# Placa_Final_Embebidos_Hoja3.net
KiCad netlist of a schematic drawn in Altium Designer
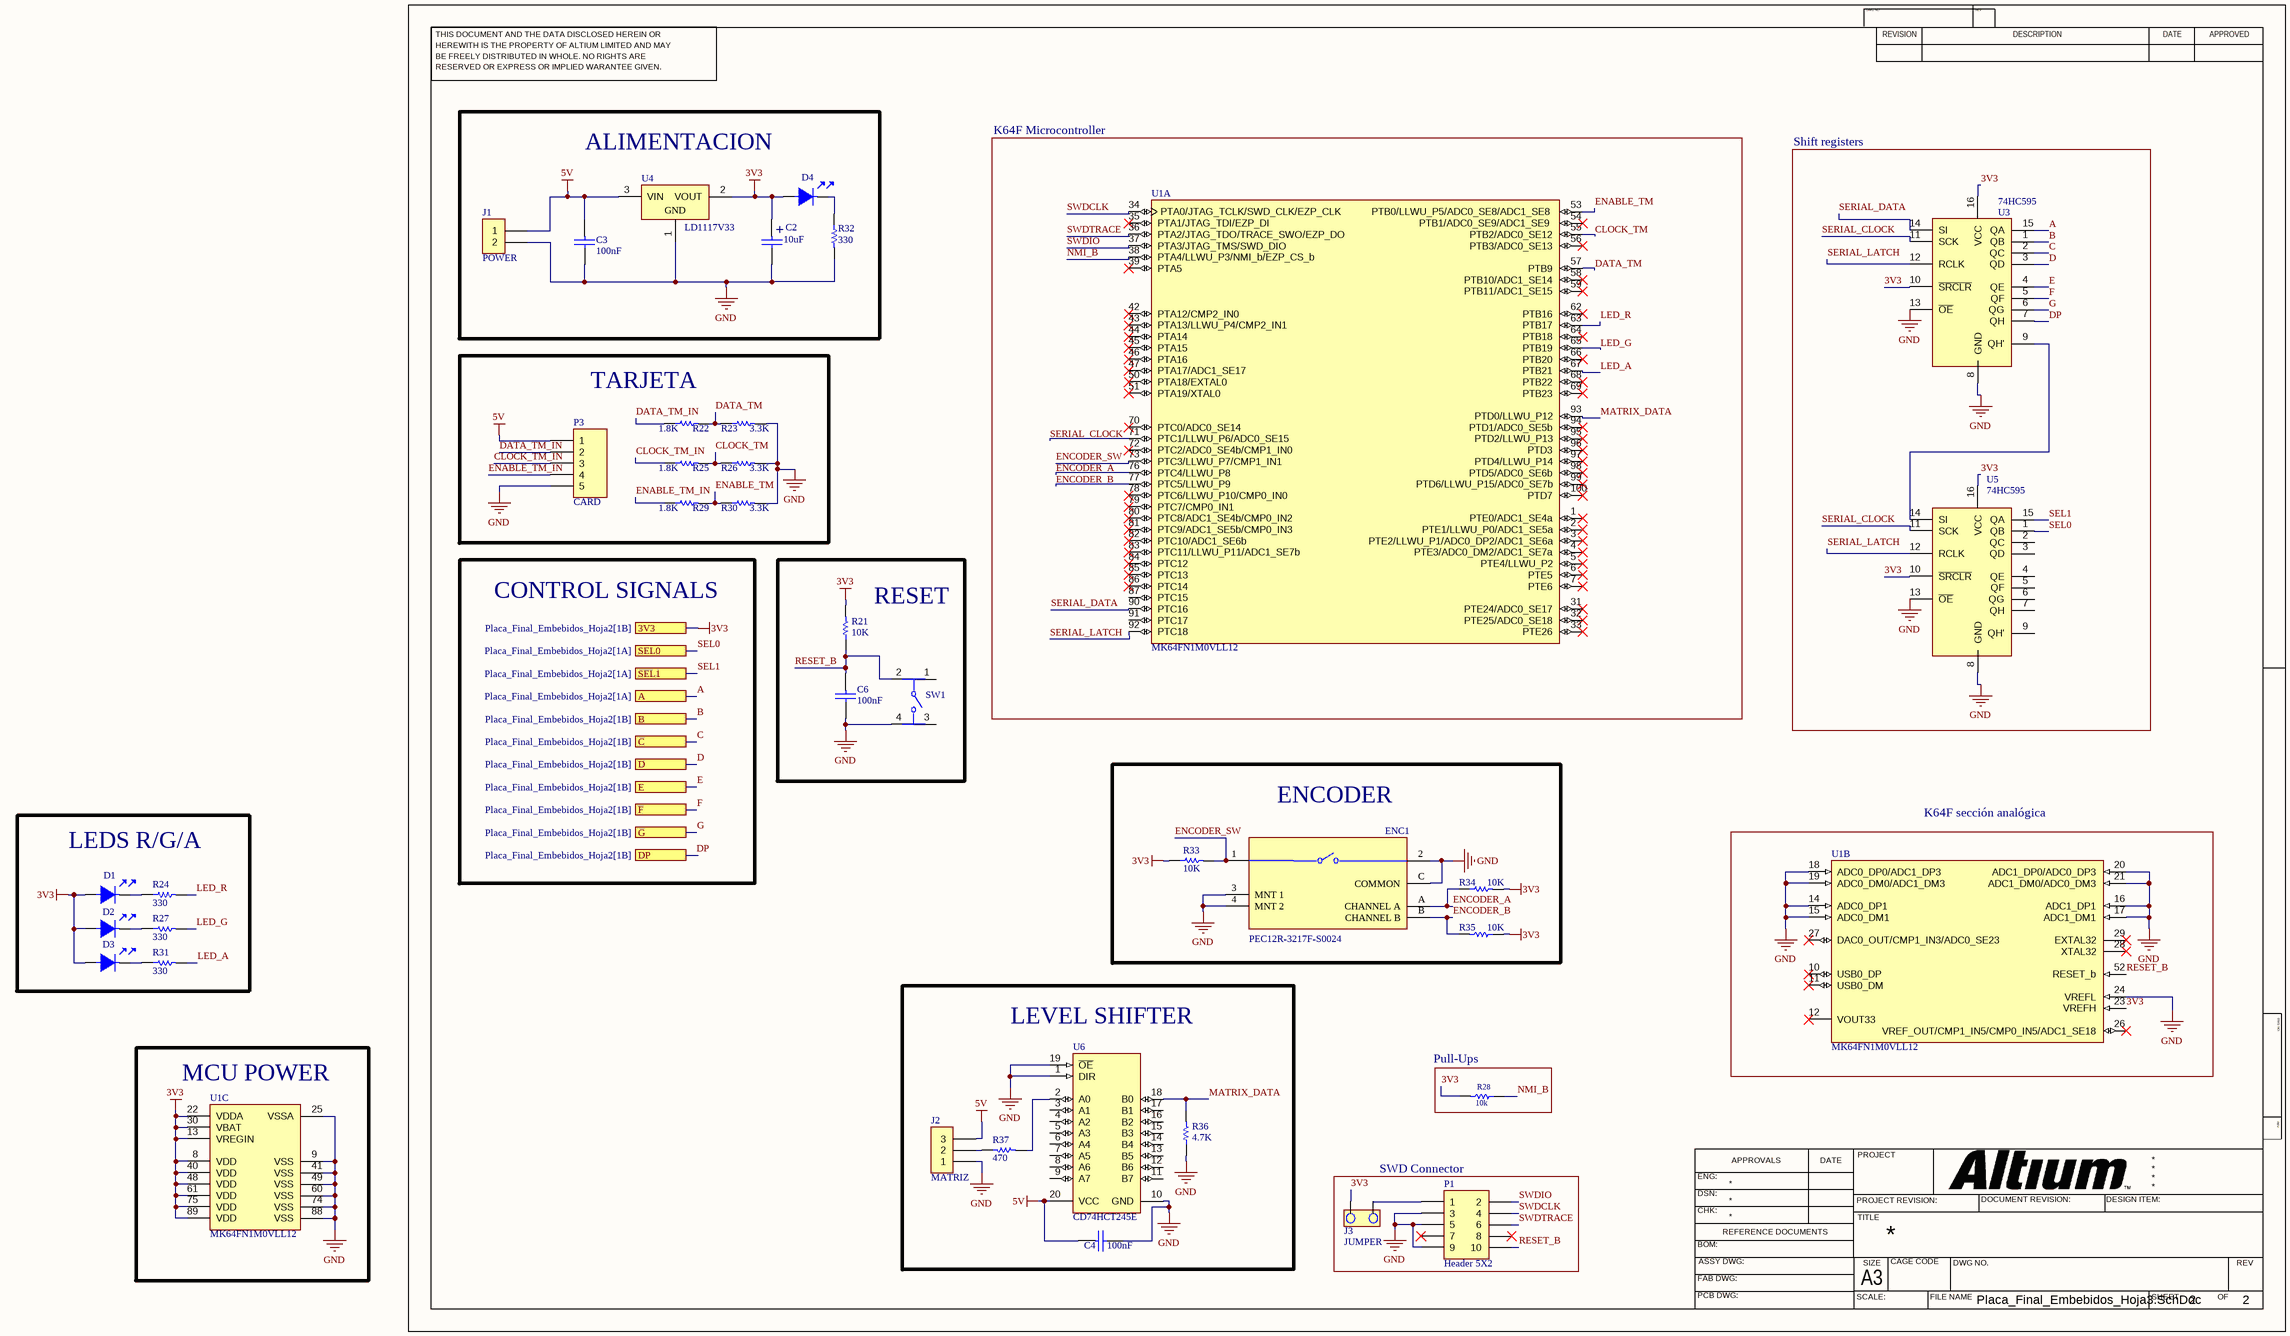
[diagram p0: Placa_Final_Embebidos_Hoja3.SchDoc]

(export (version "E")
  (design (tool "Eeschema 10.0.6"))
  (components
    (comp (ref "C2") (value "10uF") (footprint "CAP100RP") (libsource (lib "LIB PIO IX") (part "CAPPOL")))
    (comp (ref "C3") (value "100nF") (footprint "CAP200") (libsource (lib "LIB PIO IX") (part "CAP")))
    (comp (ref "C4") (value "100nF") (footprint "CAP200") (libsource (lib "LIB PIO IX") (part "CAP")))
    (comp (ref "C6") (value "100nF") (footprint "CAP200") (libsource (lib "LIB PIO IX") (part "CAP")))
    (comp (ref "D1") (value "~") (footprint "LED3") (libsource (lib "LIB PIO IX") (part "LED")))
    (comp (ref "D2") (value "~") (footprint "LED3") (libsource (lib "LIB PIO IX") (part "LED")))
    (comp (ref "D3") (value "~") (footprint "LED3") (libsource (lib "LIB PIO IX") (part "LED")))
    (comp (ref "D4") (value "~") (footprint "LED3") (libsource (lib "LIB PIO IX") (part "LED")))
    (comp (ref "ENC1")
      (value "PEC12R-3217F-S0024")
      (footprint "FP-PEC12R-3217F-S0024-MFG")
      (description "ROTARY ENCODER")
      (libsource (lib "Altium Content Vault") (part "795c46dd6d7d77f565e7c060d07d204"))
    )
    (comp (ref "J1") (value "POWER") (footprint "BORNERA2") (libsource (lib "LIBEBAL") (part "BORNERA 2")))
    (comp (ref "J2") (value "MATRIZ") (footprint "SIP3") (libsource (lib "LIBEBAL") (part "CON3")))
    (comp (ref "J3") (value "JUMPER") (footprint "JUMPER2") (libsource (lib "LIBEBAL") (part "JUMPER")))
    (comp (ref "P1")
      (value "Header 5X2")
      (footprint "HDR2X5")
      (description "Header, 5-Pin, Dual row")
      (fields (field (name "PUBLISHER") "Altium Limited"))
      (libsource (lib "Miscellaneous Connectors") (part "Header 5X2"))
    )
    (comp (ref "P3")
      (value "CARD")
      (footprint "HDR1X5")
      (description "Header, 5-Pin")
      (fields (field (name "PUBLISHER") "Altium Limited"))
      (libsource (lib "Miscellaneous Connectors") (part "Header 5"))
    )
    (comp (ref "R21") (value "10K") (footprint "RES400") (libsource (lib "LIB PIO IX") (part "RES")))
    (comp (ref "R22") (value "1.8K") (footprint "RES400") (libsource (lib "LIB PIO IX") (part "RES")))
    (comp (ref "R23") (value "3.3K") (footprint "RES400") (libsource (lib "LIB PIO IX") (part "RES")))
    (comp (ref "R24") (value "330") (footprint "RES400") (libsource (lib "LIB PIO IX") (part "RES")))
    (comp (ref "R25") (value "1.8K") (footprint "RES400") (libsource (lib "LIB PIO IX") (part "RES")))
    (comp (ref "R26") (value "3.3K") (footprint "RES400") (libsource (lib "LIB PIO IX") (part "RES")))
    (comp (ref "R27") (value "330") (footprint "RES400") (libsource (lib "LIB PIO IX") (part "RES")))
    (comp (ref "R28") (value "10k") (footprint "RES400") (libsource (lib "LIB PIO IX") (part "RES")))
    (comp (ref "R29") (value "1.8K") (footprint "RES400") (libsource (lib "LIB PIO IX") (part "RES")))
    (comp (ref "R30") (value "3.3K") (footprint "RES400") (libsource (lib "LIB PIO IX") (part "RES")))
    (comp (ref "R31") (value "330") (footprint "RES400") (libsource (lib "LIB PIO IX") (part "RES")))
    (comp (ref "R32") (value "330") (footprint "RES400") (libsource (lib "LIB PIO IX") (part "RES")))
    (comp (ref "R33") (value "10K") (footprint "RES400") (libsource (lib "LIB PIO IX") (part "RES")))
    (comp (ref "R34") (value "10K") (footprint "RES400") (libsource (lib "LIB PIO IX") (part "RES")))
    (comp (ref "R35") (value "10K") (footprint "RES400") (libsource (lib "LIB PIO IX") (part "RES")))
    (comp (ref "R36") (value "4.7K") (footprint "RES400") (libsource (lib "LIB PIO IX") (part "RES")))
    (comp (ref "R37") (value "470") (footprint "RES400") (libsource (lib "LIB PIO IX") (part "RES")))
    (comp (ref "SW1")
      (value "~")
      (footprint "FP-B3F-1055-MFG")
      (description "SWITCH TACTILE SPST-NO 0.05A 24V")
      (libsource (lib "Altium Content Vault") (part "b8895f3f4cefb76e1819d2863dba89b"))
    )
    (comp (ref "U1")
      (value "MK64FN1M0VLL12")
      (footprint "PCB_BOARD_K64F_MIRROR:K64F_DevBoard_Headers_MIRROR")
      (fields (field (name "MANUFACTURER") "Freescale Semiconductor"))
      (libsource (lib "K64F_Board_MIRROR") (part "CMP-0182-00049-1"))
    )
    (comp (ref "U3") (value "74HC595") (footprint "DIP16") (libsource (lib "LIBEBAL") (part "74HC595")))
    (comp (ref "U4")
      (value "LD1117V33")
      (footprint "TO220")
      (description "Fixed Low Drop Positive Voltage Regulator, 3.3V, 3-Pin TO-220")
      (libsource (lib "Altium Content Vault") (part "PM-REG-LD1117V-SIL3"))
    )
    (comp (ref "U5") (value "74HC595") (footprint "DIP16") (libsource (lib "LIBEBAL") (part "74HC595")))
    (comp (ref "U6")
      (value "CD74HCT245E")
      (footprint "N0020A")
      (description "High Speed CMOS Logic Non-Inverting Octal-Bus Transceiver with 3-State Outpus, N0020A, TUBE")
      (fields
        (field (name "GENERIC PART NUMBER") "CD74HCT245")
        (field (name "MANUFACTURER") "Texas Instruments")
      )
      (libsource (lib "Altium Content Vault") (part "TI-CD54_74XXX245_640-20"))
    )
  )
  (nets
    (net (code "1") (name "/A") (class "Default")
      (node (ref "U3") (pin "15") (pinfunction "QA_15") (pintype "passive"))
    )
    (net (code "2") (name "/B") (class "Default")
      (node (ref "U3") (pin "1") (pinfunction "QB_1") (pintype "passive"))
    )
    (net (code "3") (name "/C") (class "Default")
      (node (ref "U3") (pin "2") (pinfunction "QC_2") (pintype "passive"))
    )
    (net (code "4") (name "/CLOCK_TM") (class "Default")
      (node (ref "R25") (pin "2") (pinfunction "2_2") (pintype "passive"))
      (node (ref "R26") (pin "1") (pinfunction "1_1") (pintype "passive"))
      (node (ref "U1") (pin "55") (pinfunction "PTB2/ADC0_SE12_55") (pintype "bidirectional"))
    )
    (net (code "5") (name "/CLOCK_TM_IN") (class "Default")
      (node (ref "P3") (pin "3") (pinfunction "3_3") (pintype "passive"))
      (node (ref "R25") (pin "1") (pinfunction "1_1") (pintype "passive"))
    )
    (net (code "6") (name "/D") (class "Default")
      (node (ref "U3") (pin "3") (pinfunction "QD_3") (pintype "passive"))
    )
    (net (code "7") (name "/DATA_TM") (class "Default")
      (node (ref "R22") (pin "2") (pinfunction "2_2") (pintype "passive"))
      (node (ref "R23") (pin "1") (pinfunction "1_1") (pintype "passive"))
      (node (ref "U1") (pin "57") (pinfunction "PTB9_57") (pintype "bidirectional"))
    )
    (net (code "8") (name "/DATA_TM_IN") (class "Default")
      (node (ref "P3") (pin "2") (pinfunction "2_2") (pintype "passive"))
      (node (ref "R22") (pin "1") (pinfunction "1_1") (pintype "passive"))
    )
    (net (code "9") (name "/DP") (class "Default")
      (node (ref "U3") (pin "7") (pinfunction "QH_7") (pintype "passive"))
    )
    (net (code "10") (name "/E") (class "Default")
      (node (ref "U3") (pin "4") (pinfunction "QE_4") (pintype "passive"))
    )
    (net (code "11") (name "/ENABLE_TM") (class "Default")
      (node (ref "R29") (pin "2") (pinfunction "2_2") (pintype "passive"))
      (node (ref "R30") (pin "1") (pinfunction "1_1") (pintype "passive"))
      (node (ref "U1") (pin "53") (pinfunction "PTB0/LLWU_P5/ADC0_SE8/ADC1_SE8_53") (pintype "bidirectional"))
    )
    (net (code "12") (name "/ENABLE_TM_IN") (class "Default")
      (node (ref "P3") (pin "4") (pinfunction "4_4") (pintype "passive"))
      (node (ref "R29") (pin "1") (pinfunction "1_1") (pintype "passive"))
    )
    (net (code "13") (name "/ENCODER_A") (class "Default")
      (node (ref "ENC1") (pin "A") (pinfunction "CHANNEL_A_A") (pintype "passive"))
      (node (ref "R34") (pin "1") (pinfunction "1_1") (pintype "passive"))
      (node (ref "U1") (pin "76") (pinfunction "PTC4/LLWU_P8_76") (pintype "bidirectional"))
    )
    (net (code "14") (name "/ENCODER_B") (class "Default")
      (node (ref "ENC1") (pin "B") (pinfunction "CHANNEL_B_B") (pintype "passive"))
      (node (ref "R35") (pin "2") (pinfunction "2_2") (pintype "passive"))
      (node (ref "U1") (pin "77") (pinfunction "PTC5/LLWU_P9_77") (pintype "bidirectional"))
    )
    (net (code "15") (name "/ENCODER_SW") (class "Default")
      (node (ref "ENC1") (pin "1") (pinfunction "1_1") (pintype "passive"))
      (node (ref "R33") (pin "2") (pinfunction "2_2") (pintype "passive"))
      (node (ref "U1") (pin "73") (pinfunction "PTC3/LLWU_P7/CMP1_IN1_73") (pintype "bidirectional"))
    )
    (net (code "16") (name "/F") (class "Default")
      (node (ref "U3") (pin "5") (pinfunction "QF_5") (pintype "passive"))
    )
    (net (code "17") (name "/G") (class "Default")
      (node (ref "U3") (pin "6") (pinfunction "QG_6") (pintype "passive"))
    )
    (net (code "18") (name "/LED_A") (class "Default")
      (node (ref "R31") (pin "2") (pinfunction "2_2") (pintype "passive"))
      (node (ref "U1") (pin "67") (pinfunction "PTB21_67") (pintype "bidirectional"))
    )
    (net (code "19") (name "/LED_G") (class "Default")
      (node (ref "R27") (pin "2") (pinfunction "2_2") (pintype "passive"))
      (node (ref "U1") (pin "65") (pinfunction "PTB19_65") (pintype "bidirectional"))
    )
    (net (code "20") (name "/LED_R") (class "Default")
      (node (ref "R24") (pin "2") (pinfunction "2_2") (pintype "passive"))
      (node (ref "U1") (pin "63") (pinfunction "PTB17_63") (pintype "bidirectional"))
    )
    (net (code "21") (name "/MATRIX_DATA") (class "Default")
      (node (ref "R36") (pin "2") (pinfunction "2_2") (pintype "passive"))
      (node (ref "U1") (pin "93") (pinfunction "PTD0/LLWU_P12_93") (pintype "bidirectional"))
      (node (ref "U6") (pin "18") (pinfunction "B0_18") (pintype "bidirectional"))
    )
    (net (code "22") (name "/NMI_B") (class "Default")
      (node (ref "R28") (pin "1") (pinfunction "1_1") (pintype "passive"))
      (node (ref "U1") (pin "38") (pinfunction "PTA4/LLWU_P3/NMI_b/EZP_CS_b_38") (pintype "bidirectional"))
    )
    (net (code "23") (name "/RESET_B") (class "Default")
      (node (ref "C6") (pin "1") (pinfunction "1_1") (pintype "passive"))
      (node (ref "P1") (pin "10") (pinfunction "10_10") (pintype "passive"))
      (node (ref "R21") (pin "1") (pinfunction "1_1") (pintype "passive"))
      (node (ref "SW1") (pin "2") (pinfunction "2_2") (pintype "passive"))
      (node (ref "U1") (pin "52") (pinfunction "RESET_b_52") (pintype "input"))
    )
    (net (code "24") (name "/SEL0") (class "Default")
      (node (ref "U5") (pin "1") (pinfunction "QB_1") (pintype "passive"))
    )
    (net (code "25") (name "/SEL1") (class "Default")
      (node (ref "U5") (pin "15") (pinfunction "QA_15") (pintype "passive"))
    )
    (net (code "26") (name "/SERIAL_CLOCK") (class "Default")
      (node (ref "U1") (pin "71") (pinfunction "PTC1/LLWU_P6/ADC0_SE15_71") (pintype "bidirectional"))
      (node (ref "U3") (pin "11") (pinfunction "SCK_11") (pintype "passive"))
      (node (ref "U5") (pin "11") (pinfunction "SCK_11") (pintype "passive"))
    )
    (net (code "27") (name "/SERIAL_DATA") (class "Default")
      (node (ref "U1") (pin "90") (pinfunction "PTC16_90") (pintype "bidirectional"))
      (node (ref "U3") (pin "14") (pinfunction "SI_14") (pintype "passive"))
    )
    (net (code "28") (name "/SERIAL_LATCH") (class "Default")
      (node (ref "U1") (pin "92") (pinfunction "PTC18_92") (pintype "bidirectional"))
      (node (ref "U3") (pin "12") (pinfunction "RCLK_12") (pintype "passive"))
      (node (ref "U5") (pin "12") (pinfunction "RCLK_12") (pintype "passive"))
    )
    (net (code "29") (name "/SWDCLK") (class "Default")
      (node (ref "P1") (pin "4") (pinfunction "4_4") (pintype "passive"))
      (node (ref "U1") (pin "34") (pinfunction "PTA0/JTAG_TCLK/SWD_CLK/EZP_CLK_34") (pintype "bidirectional"))
    )
    (net (code "30") (name "/SWDIO") (class "Default")
      (node (ref "P1") (pin "2") (pinfunction "2_2") (pintype "passive"))
      (node (ref "U1") (pin "37") (pinfunction "PTA3/JTAG_TMS/SWD_DIO_37") (pintype "bidirectional"))
    )
    (net (code "31") (name "/SWDTRACE") (class "Default")
      (node (ref "P1") (pin "6") (pinfunction "6_6") (pintype "passive"))
      (node (ref "U1") (pin "36") (pinfunction "PTA2/JTAG_TDO/TRACE_SWO/EZP_DO_36") (pintype "bidirectional"))
    )
    (net (code "32") (name "3V3") (class "Default")
      (node (ref "C2") (pin "1") (pinfunction "1_1") (pintype "passive"))
      (node (ref "D1") (pin "1") (pinfunction "1_1") (pintype "passive"))
      (node (ref "D2") (pin "1") (pinfunction "1_1") (pintype "passive"))
      (node (ref "D3") (pin "1") (pinfunction "1_1") (pintype "passive"))
      (node (ref "D4") (pin "1") (pinfunction "1_1") (pintype "passive"))
      (node (ref "J3") (pin "1") (pinfunction "1_1") (pintype "passive"))
      (node (ref "R21") (pin "2") (pinfunction "2_2") (pintype "passive"))
      (node (ref "R28") (pin "2") (pinfunction "2_2") (pintype "passive"))
      (node (ref "R33") (pin "1") (pinfunction "1_1") (pintype "passive"))
      (node (ref "R34") (pin "2") (pinfunction "2_2") (pintype "passive"))
      (node (ref "R35") (pin "1") (pinfunction "1_1") (pintype "passive"))
      (node (ref "U1") (pin "13") (pinfunction "VREGIN_13") (pintype "power_in"))
      (node (ref "U1") (pin "22") (pinfunction "VDDA_22") (pintype "power_in"))
      (node (ref "U1") (pin "23") (pinfunction "VREFH_23") (pintype "input"))
      (node (ref "U1") (pin "30") (pinfunction "VBAT_30") (pintype "power_in"))
      (node (ref "U1") (pin "40") (pinfunction "VDD_40") (pintype "power_in"))
      (node (ref "U1") (pin "48") (pinfunction "VDD_48") (pintype "power_in"))
      (node (ref "U1") (pin "61") (pinfunction "VDD_61") (pintype "power_in"))
      (node (ref "U1") (pin "75") (pinfunction "VDD_75") (pintype "power_in"))
      (node (ref "U1") (pin "8") (pinfunction "VDD_8") (pintype "power_in"))
      (node (ref "U1") (pin "89") (pinfunction "VDD_89") (pintype "power_in"))
      (node (ref "U3") (pin "10") (pinfunction "~{SRCLR}_10") (pintype "passive"))
      (node (ref "U3") (pin "16") (pinfunction "VCC_16") (pintype "passive"))
      (node (ref "U4") (pin "2") (pinfunction "VOUT_2") (pintype "power_in"))
      (node (ref "U5") (pin "10") (pinfunction "~{SRCLR}_10") (pintype "passive"))
      (node (ref "U5") (pin "16") (pinfunction "VCC_16") (pintype "passive"))
    )
    (net (code "33") (name "5V") (class "Default")
      (node (ref "C3") (pin "1") (pinfunction "1_1") (pintype "passive"))
      (node (ref "C4") (pin "1") (pinfunction "1_1") (pintype "passive"))
      (node (ref "J1") (pin "1") (pinfunction "1_1") (pintype "passive"))
      (node (ref "J2") (pin "3") (pinfunction "3_3") (pintype "passive"))
      (node (ref "P3") (pin "1") (pinfunction "1_1") (pintype "passive"))
      (node (ref "U4") (pin "3") (pinfunction "VIN_3") (pintype "power_in"))
      (node (ref "U6") (pin "20") (pinfunction "VCC_20") (pintype "power_in"))
    )
    (net (code "34") (name "GND") (class "Default")
      (node (ref "C2") (pin "2") (pinfunction "2_2") (pintype "passive"))
      (node (ref "C3") (pin "2") (pinfunction "2_2") (pintype "passive"))
      (node (ref "C4") (pin "2") (pinfunction "2_2") (pintype "passive"))
      (node (ref "C6") (pin "2") (pinfunction "2_2") (pintype "passive"))
      (node (ref "ENC1") (pin "2") (pinfunction "2_2") (pintype "passive"))
      (node (ref "ENC1") (pin "3") (pinfunction "MNT_1_3") (pintype "passive"))
      (node (ref "ENC1") (pin "4") (pinfunction "MNT_2_4") (pintype "passive"))
      (node (ref "ENC1") (pin "C") (pinfunction "COMMON_C") (pintype "passive"))
      (node (ref "J1") (pin "2") (pinfunction "2_2") (pintype "passive"))
      (node (ref "J2") (pin "1") (pinfunction "1_1") (pintype "passive"))
      (node (ref "P1") (pin "3") (pinfunction "3_3") (pintype "passive"))
      (node (ref "P1") (pin "5") (pinfunction "5_5") (pintype "passive"))
      (node (ref "P1") (pin "9") (pinfunction "9_9") (pintype "passive"))
      (node (ref "P3") (pin "5") (pinfunction "5_5") (pintype "passive"))
      (node (ref "R23") (pin "2") (pinfunction "2_2") (pintype "passive"))
      (node (ref "R26") (pin "2") (pinfunction "2_2") (pintype "passive"))
      (node (ref "R30") (pin "2") (pinfunction "2_2") (pintype "passive"))
      (node (ref "R32") (pin "2") (pinfunction "2_2") (pintype "passive"))
      (node (ref "R36") (pin "1") (pinfunction "1_1") (pintype "passive"))
      (node (ref "SW1") (pin "4") (pinfunction "4_4") (pintype "passive"))
      (node (ref "U1") (pin "14") (pinfunction "ADC0_DP1_14") (pintype "input"))
      (node (ref "U1") (pin "15") (pinfunction "ADC0_DM1_15") (pintype "input"))
      (node (ref "U1") (pin "16") (pinfunction "ADC1_DP1_16") (pintype "input"))
      (node (ref "U1") (pin "17") (pinfunction "ADC1_DM1_17") (pintype "input"))
      (node (ref "U1") (pin "18") (pinfunction "ADC0_DP0/ADC1_DP3_18") (pintype "input"))
      (node (ref "U1") (pin "19") (pinfunction "ADC0_DM0/ADC1_DM3_19") (pintype "input"))
      (node (ref "U1") (pin "20") (pinfunction "ADC1_DP0/ADC0_DP3_20") (pintype "input"))
      (node (ref "U1") (pin "21") (pinfunction "ADC1_DM0/ADC0_DM3_21") (pintype "input"))
      (node (ref "U1") (pin "24") (pinfunction "VREFL_24") (pintype "input"))
      (node (ref "U1") (pin "25") (pinfunction "VSSA_25") (pintype "power_in"))
      (node (ref "U1") (pin "41") (pinfunction "VSS_41") (pintype "power_in"))
      (node (ref "U1") (pin "49") (pinfunction "VSS_49") (pintype "power_in"))
      (node (ref "U1") (pin "60") (pinfunction "VSS_60") (pintype "power_in"))
      (node (ref "U1") (pin "74") (pinfunction "VSS_74") (pintype "power_in"))
      (node (ref "U1") (pin "88") (pinfunction "VSS_88") (pintype "power_in"))
      (node (ref "U1") (pin "9") (pinfunction "VSS_9") (pintype "power_in"))
      (node (ref "U3") (pin "13") (pinfunction "~{OE}_13") (pintype "passive"))
      (node (ref "U3") (pin "8") (pinfunction "GND_8") (pintype "passive"))
      (node (ref "U4") (pin "1") (pinfunction "GND_1") (pintype "power_in"))
      (node (ref "U5") (pin "13") (pinfunction "~{OE}_13") (pintype "passive"))
      (node (ref "U5") (pin "8") (pinfunction "GND_8") (pintype "passive"))
      (node (ref "U6") (pin "1") (pinfunction "DIR_1") (pintype "input"))
      (node (ref "U6") (pin "10") (pinfunction "GND_10") (pintype "power_in"))
      (node (ref "U6") (pin "19") (pinfunction "~{OE}_19") (pintype "input"))
    )
    (net (code "35") (name "Net-(D1-Pad2)") (class "Default")
      (node (ref "D1") (pin "2") (pinfunction "2_2") (pintype "passive"))
      (node (ref "R24") (pin "1") (pinfunction "1_1") (pintype "passive"))
    )
    (net (code "36") (name "Net-(D2-Pad2)") (class "Default")
      (node (ref "D2") (pin "2") (pinfunction "2_2") (pintype "passive"))
      (node (ref "R27") (pin "1") (pinfunction "1_1") (pintype "passive"))
    )
    (net (code "37") (name "Net-(D3-Pad2)") (class "Default")
      (node (ref "D3") (pin "2") (pinfunction "2_2") (pintype "passive"))
      (node (ref "R31") (pin "1") (pinfunction "1_1") (pintype "passive"))
    )
    (net (code "38") (name "Net-(D4-Pad2)") (class "Default")
      (node (ref "D4") (pin "2") (pinfunction "2_2") (pintype "passive"))
      (node (ref "R32") (pin "1") (pinfunction "1_1") (pintype "passive"))
    )
    (net (code "39") (name "Net-(J2-Pad2)") (class "Default")
      (node (ref "J2") (pin "2") (pinfunction "2_2") (pintype "passive"))
      (node (ref "R37") (pin "1") (pinfunction "1_1") (pintype "passive"))
    )
    (net (code "40") (name "Net-(J3-Pad2)") (class "Default")
      (node (ref "J3") (pin "2") (pinfunction "2_2") (pintype "passive"))
      (node (ref "P1") (pin "1") (pinfunction "1_1") (pintype "passive"))
    )
    (net (code "41") (name "Net-(U3-QH')") (class "Default")
      (node (ref "U3") (pin "9") (pinfunction "QH'_9") (pintype "passive"))
      (node (ref "U5") (pin "14") (pinfunction "SI_14") (pintype "passive"))
    )
    (net (code "42") (name "Net-(U6-A0)") (class "Default")
      (node (ref "R37") (pin "2") (pinfunction "2_2") (pintype "passive"))
      (node (ref "U6") (pin "2") (pinfunction "A0_2") (pintype "bidirectional"))
    )
    (net (code "43") (name "unconnected-(P1-Pad7)") (class "Default")
      (node (ref "P1") (pin "7") (pinfunction "7_7") (pintype "passive+no_connect"))
    )
    (net (code "44") (name "unconnected-(P1-Pad8)") (class "Default")
      (node (ref "P1") (pin "8") (pinfunction "8_8") (pintype "passive+no_connect"))
    )
    (net (code "45") (name "unconnected-(SW1-Pad1)") (class "Default")
      (node (ref "SW1") (pin "1") (pinfunction "1_1") (pintype "passive"))
    )
    (net (code "46") (name "unconnected-(SW1-Pad3)") (class "Default")
      (node (ref "SW1") (pin "3") (pinfunction "3_3") (pintype "passive"))
    )
    (net (code "47") (name "unconnected-(U1A-PTA1{slash}JTAG_TDI{slash}EZP_DI-Pad35)") (class "Default")
      (node (ref "U1") (pin "35") (pinfunction "PTA1/JTAG_TDI/EZP_DI_35") (pintype "bidirectional+no_connect"))
    )
    (net (code "48") (name "unconnected-(U1A-PTA5-Pad39)") (class "Default")
      (node (ref "U1") (pin "39") (pinfunction "PTA5_39") (pintype "bidirectional+no_connect"))
    )
    (net (code "49") (name "unconnected-(U1A-PTA12{slash}CMP2_IN0-Pad42)") (class "Default")
      (node (ref "U1") (pin "42") (pinfunction "PTA12/CMP2_IN0_42") (pintype "bidirectional+no_connect"))
    )
    (net (code "50") (name "unconnected-(U1A-PTA13{slash}LLWU_P4{slash}CMP2_IN1-Pad43)") (class "Default")
      (node (ref "U1") (pin "43") (pinfunction "PTA13/LLWU_P4/CMP2_IN1_43") (pintype "bidirectional+no_connect"))
    )
    (net (code "51") (name "unconnected-(U1A-PTA14-Pad44)") (class "Default")
      (node (ref "U1") (pin "44") (pinfunction "PTA14_44") (pintype "bidirectional+no_connect"))
    )
    (net (code "52") (name "unconnected-(U1A-PTA15-Pad45)") (class "Default")
      (node (ref "U1") (pin "45") (pinfunction "PTA15_45") (pintype "bidirectional+no_connect"))
    )
    (net (code "53") (name "unconnected-(U1A-PTA16-Pad46)") (class "Default")
      (node (ref "U1") (pin "46") (pinfunction "PTA16_46") (pintype "bidirectional+no_connect"))
    )
    (net (code "54") (name "unconnected-(U1A-PTA17{slash}ADC1_SE17-Pad47)") (class "Default")
      (node (ref "U1") (pin "47") (pinfunction "PTA17/ADC1_SE17_47") (pintype "bidirectional+no_connect"))
    )
    (net (code "55") (name "unconnected-(U1A-PTA18{slash}EXTAL0-Pad50)") (class "Default")
      (node (ref "U1") (pin "50") (pinfunction "PTA18/EXTAL0_50") (pintype "bidirectional+no_connect"))
    )
    (net (code "56") (name "unconnected-(U1A-PTA19{slash}XTAL0-Pad51)") (class "Default")
      (node (ref "U1") (pin "51") (pinfunction "PTA19/XTAL0_51") (pintype "bidirectional+no_connect"))
    )
    (net (code "57") (name "unconnected-(U1A-PTB1{slash}ADC0_SE9{slash}ADC1_SE9-Pad54)") (class "Default")
      (node (ref "U1") (pin "54") (pinfunction "PTB1/ADC0_SE9/ADC1_SE9_54") (pintype "bidirectional+no_connect"))
    )
    (net (code "58") (name "unconnected-(U1A-PTB3{slash}ADC0_SE13-Pad56)") (class "Default")
      (node (ref "U1") (pin "56") (pinfunction "PTB3/ADC0_SE13_56") (pintype "bidirectional+no_connect"))
    )
    (net (code "59") (name "unconnected-(U1A-PTB10{slash}ADC1_SE14-Pad58)") (class "Default")
      (node (ref "U1") (pin "58") (pinfunction "PTB10/ADC1_SE14_58") (pintype "bidirectional+no_connect"))
    )
    (net (code "60") (name "unconnected-(U1A-PTB11{slash}ADC1_SE15-Pad59)") (class "Default")
      (node (ref "U1") (pin "59") (pinfunction "PTB11/ADC1_SE15_59") (pintype "bidirectional+no_connect"))
    )
    (net (code "61") (name "unconnected-(U1A-PTB16-Pad62)") (class "Default")
      (node (ref "U1") (pin "62") (pinfunction "PTB16_62") (pintype "bidirectional+no_connect"))
    )
    (net (code "62") (name "unconnected-(U1A-PTB18-Pad64)") (class "Default")
      (node (ref "U1") (pin "64") (pinfunction "PTB18_64") (pintype "bidirectional+no_connect"))
    )
    (net (code "63") (name "unconnected-(U1A-PTB20-Pad66)") (class "Default")
      (node (ref "U1") (pin "66") (pinfunction "PTB20_66") (pintype "bidirectional+no_connect"))
    )
    (net (code "64") (name "unconnected-(U1A-PTB22-Pad68)") (class "Default")
      (node (ref "U1") (pin "68") (pinfunction "PTB22_68") (pintype "bidirectional+no_connect"))
    )
    (net (code "65") (name "unconnected-(U1A-PTB23-Pad69)") (class "Default")
      (node (ref "U1") (pin "69") (pinfunction "PTB23_69") (pintype "bidirectional+no_connect"))
    )
    (net (code "66") (name "unconnected-(U1A-PTC0{slash}ADC0_SE14-Pad70)") (class "Default")
      (node (ref "U1") (pin "70") (pinfunction "PTC0/ADC0_SE14_70") (pintype "bidirectional+no_connect"))
    )
    (net (code "67") (name "unconnected-(U1A-PTC2{slash}ADC0_SE4b{slash}CMP1_IN0-Pad72)") (class "Default")
      (node (ref "U1") (pin "72") (pinfunction "PTC2/ADC0_SE4b/CMP1_IN0_72") (pintype "bidirectional+no_connect"))
    )
    (net (code "68") (name "unconnected-(U1A-PTC6{slash}LLWU_P10{slash}CMP0_IN0-Pad78)") (class "Default")
      (node (ref "U1") (pin "78") (pinfunction "PTC6/LLWU_P10/CMP0_IN0_78") (pintype "bidirectional+no_connect"))
    )
    (net (code "69") (name "unconnected-(U1A-PTC7{slash}CMP0_IN1-Pad79)") (class "Default")
      (node (ref "U1") (pin "79") (pinfunction "PTC7/CMP0_IN1_79") (pintype "bidirectional+no_connect"))
    )
    (net (code "70") (name "unconnected-(U1A-PTC8{slash}ADC1_SE4b{slash}CMP0_IN2-Pad80)") (class "Default")
      (node (ref "U1") (pin "80") (pinfunction "PTC8/ADC1_SE4b/CMP0_IN2_80") (pintype "bidirectional+no_connect"))
    )
    (net (code "71") (name "unconnected-(U1A-PTC9{slash}ADC1_SE5b{slash}CMP0_IN3-Pad81)") (class "Default")
      (node (ref "U1") (pin "81") (pinfunction "PTC9/ADC1_SE5b/CMP0_IN3_81") (pintype "bidirectional+no_connect"))
    )
    (net (code "72") (name "unconnected-(U1A-PTC10{slash}ADC1_SE6b-Pad82)") (class "Default")
      (node (ref "U1") (pin "82") (pinfunction "PTC10/ADC1_SE6b_82") (pintype "bidirectional+no_connect"))
    )
    (net (code "73") (name "unconnected-(U1A-PTC11{slash}LLWU_P11{slash}ADC1_SE7b-Pad83)") (class "Default")
      (node (ref "U1") (pin "83") (pinfunction "PTC11/LLWU_P11/ADC1_SE7b_83") (pintype "bidirectional+no_connect"))
    )
    (net (code "74") (name "unconnected-(U1A-PTC12-Pad84)") (class "Default")
      (node (ref "U1") (pin "84") (pinfunction "PTC12_84") (pintype "bidirectional+no_connect"))
    )
    (net (code "75") (name "unconnected-(U1A-PTC13-Pad85)") (class "Default")
      (node (ref "U1") (pin "85") (pinfunction "PTC13_85") (pintype "bidirectional+no_connect"))
    )
    (net (code "76") (name "unconnected-(U1A-PTC14-Pad86)") (class "Default")
      (node (ref "U1") (pin "86") (pinfunction "PTC14_86") (pintype "bidirectional+no_connect"))
    )
    (net (code "77") (name "unconnected-(U1A-PTC15-Pad87)") (class "Default")
      (node (ref "U1") (pin "87") (pinfunction "PTC15_87") (pintype "bidirectional"))
    )
    (net (code "78") (name "unconnected-(U1A-PTC17-Pad91)") (class "Default")
      (node (ref "U1") (pin "91") (pinfunction "PTC17_91") (pintype "bidirectional"))
    )
    (net (code "79") (name "unconnected-(U1A-PTD1{slash}ADC0_SE5b-Pad94)") (class "Default")
      (node (ref "U1") (pin "94") (pinfunction "PTD1/ADC0_SE5b_94") (pintype "bidirectional+no_connect"))
    )
    (net (code "80") (name "unconnected-(U1A-PTD2{slash}LLWU_P13-Pad95)") (class "Default")
      (node (ref "U1") (pin "95") (pinfunction "PTD2/LLWU_P13_95") (pintype "bidirectional+no_connect"))
    )
    (net (code "81") (name "unconnected-(U1A-PTD3-Pad96)") (class "Default")
      (node (ref "U1") (pin "96") (pinfunction "PTD3_96") (pintype "bidirectional+no_connect"))
    )
    (net (code "82") (name "unconnected-(U1A-PTD4{slash}LLWU_P14-Pad97)") (class "Default")
      (node (ref "U1") (pin "97") (pinfunction "PTD4/LLWU_P14_97") (pintype "bidirectional+no_connect"))
    )
    (net (code "83") (name "unconnected-(U1A-PTD5{slash}ADC0_SE6b-Pad98)") (class "Default")
      (node (ref "U1") (pin "98") (pinfunction "PTD5/ADC0_SE6b_98") (pintype "bidirectional+no_connect"))
    )
    (net (code "84") (name "unconnected-(U1A-PTD6{slash}LLWU_P15{slash}ADC0_SE7b-Pad99)") (class "Default")
      (node (ref "U1") (pin "99") (pinfunction "PTD6/LLWU_P15/ADC0_SE7b_99") (pintype "bidirectional+no_connect"))
    )
    (net (code "85") (name "unconnected-(U1A-PTD7-Pad100)") (class "Default")
      (node (ref "U1") (pin "100") (pinfunction "PTD7_100") (pintype "bidirectional+no_connect"))
    )
    (net (code "86") (name "unconnected-(U1A-PTE0{slash}ADC1_SE4a-Pad1)") (class "Default")
      (node (ref "U1") (pin "1") (pinfunction "PTE0/ADC1_SE4a_1") (pintype "bidirectional+no_connect"))
    )
    (net (code "87") (name "unconnected-(U1A-PTE1{slash}LLWU_P0{slash}ADC1_SE5a-Pad2)") (class "Default")
      (node (ref "U1") (pin "2") (pinfunction "PTE1/LLWU_P0/ADC1_SE5a_2") (pintype "bidirectional+no_connect"))
    )
    (net (code "88") (name "unconnected-(U1A-PTE2{slash}LLWU_P1{slash}ADC0_DP2{slash}ADC1_SE6a-Pad3)") (class "Default")
      (node (ref "U1") (pin "3") (pinfunction "PTE2/LLWU_P1/ADC0_DP2/ADC1_SE6a_3") (pintype "bidirectional+no_connect"))
    )
    (net (code "89") (name "unconnected-(U1A-PTE3{slash}ADC0_DM2{slash}ADC1_SE7a-Pad4)") (class "Default")
      (node (ref "U1") (pin "4") (pinfunction "PTE3/ADC0_DM2/ADC1_SE7a_4") (pintype "bidirectional+no_connect"))
    )
    (net (code "90") (name "unconnected-(U1A-PTE4{slash}LLWU_P2-Pad5)") (class "Default")
      (node (ref "U1") (pin "5") (pinfunction "PTE4/LLWU_P2_5") (pintype "bidirectional+no_connect"))
    )
    (net (code "91") (name "unconnected-(U1A-PTE5-Pad6)") (class "Default")
      (node (ref "U1") (pin "6") (pinfunction "PTE5_6") (pintype "bidirectional+no_connect"))
    )
    (net (code "92") (name "unconnected-(U1A-PTE6-Pad7)") (class "Default")
      (node (ref "U1") (pin "7") (pinfunction "PTE6_7") (pintype "bidirectional+no_connect"))
    )
    (net (code "93") (name "unconnected-(U1A-PTE24{slash}ADC0_SE17-Pad31)") (class "Default")
      (node (ref "U1") (pin "31") (pinfunction "PTE24/ADC0_SE17_31") (pintype "bidirectional+no_connect"))
    )
    (net (code "94") (name "unconnected-(U1A-PTE25{slash}ADC0_SE18-Pad32)") (class "Default")
      (node (ref "U1") (pin "32") (pinfunction "PTE25/ADC0_SE18_32") (pintype "bidirectional+no_connect"))
    )
    (net (code "95") (name "unconnected-(U1A-PTE26-Pad33)") (class "Default")
      (node (ref "U1") (pin "33") (pinfunction "PTE26_33") (pintype "bidirectional+no_connect"))
    )
    (net (code "96") (name "unconnected-(U1B-DAC0_OUT{slash}CMP1_IN3{slash}ADC0_SE23-Pad27)") (class "Default")
      (node (ref "U1") (pin "27") (pinfunction "DAC0_OUT/CMP1_IN3/ADC0_SE23_27") (pintype "bidirectional+no_connect"))
    )
    (net (code "97") (name "unconnected-(U1B-EXTAL32-Pad29)") (class "Default")
      (node (ref "U1") (pin "29") (pinfunction "EXTAL32_29") (pintype "passive+no_connect"))
    )
    (net (code "98") (name "unconnected-(U1B-USB0_DM-Pad11)") (class "Default")
      (node (ref "U1") (pin "11") (pinfunction "USB0_DM_11") (pintype "bidirectional+no_connect"))
    )
    (net (code "99") (name "unconnected-(U1B-USB0_DP-Pad10)") (class "Default")
      (node (ref "U1") (pin "10") (pinfunction "USB0_DP_10") (pintype "bidirectional+no_connect"))
    )
    (net (code "100") (name "unconnected-(U1B-VOUT33-Pad12)") (class "Default")
      (node (ref "U1") (pin "12") (pinfunction "VOUT33_12") (pintype "power_in+no_connect"))
    )
    (net (code "101") (name "unconnected-(U1B-VREF_OUT{slash}CMP1_IN5{slash}CMP0_IN5{slash}ADC1_SE18-Pad26)") (class "Default")
      (node (ref "U1") (pin "26") (pinfunction "VREF_OUT/CMP1_IN5/CMP0_IN5/ADC1_SE18_26") (pintype "bidirectional+no_connect"))
    )
    (net (code "102") (name "unconnected-(U1B-XTAL32-Pad28)") (class "Default")
      (node (ref "U1") (pin "28") (pinfunction "XTAL32_28") (pintype "passive+no_connect"))
    )
    (net (code "103") (name "unconnected-(U5-QC-Pad2)") (class "Default")
      (node (ref "U5") (pin "2") (pinfunction "QC_2") (pintype "passive"))
    )
    (net (code "104") (name "unconnected-(U5-QD-Pad3)") (class "Default")
      (node (ref "U5") (pin "3") (pinfunction "QD_3") (pintype "passive"))
    )
    (net (code "105") (name "unconnected-(U5-QE-Pad4)") (class "Default")
      (node (ref "U5") (pin "4") (pinfunction "QE_4") (pintype "passive"))
    )
    (net (code "106") (name "unconnected-(U5-QF-Pad5)") (class "Default")
      (node (ref "U5") (pin "5") (pinfunction "QF_5") (pintype "passive"))
    )
    (net (code "107") (name "unconnected-(U5-QG-Pad6)") (class "Default")
      (node (ref "U5") (pin "6") (pinfunction "QG_6") (pintype "passive"))
    )
    (net (code "108") (name "unconnected-(U5-QH'-Pad9)") (class "Default")
      (node (ref "U5") (pin "9") (pinfunction "QH'_9") (pintype "passive"))
    )
    (net (code "109") (name "unconnected-(U5-QH-Pad7)") (class "Default")
      (node (ref "U5") (pin "7") (pinfunction "QH_7") (pintype "passive"))
    )
    (net (code "110") (name "unconnected-(U6-A1-Pad3)") (class "Default")
      (node (ref "U6") (pin "3") (pinfunction "A1_3") (pintype "bidirectional"))
    )
    (net (code "111") (name "unconnected-(U6-A2-Pad4)") (class "Default")
      (node (ref "U6") (pin "4") (pinfunction "A2_4") (pintype "bidirectional"))
    )
    (net (code "112") (name "unconnected-(U6-A3-Pad5)") (class "Default")
      (node (ref "U6") (pin "5") (pinfunction "A3_5") (pintype "bidirectional"))
    )
    (net (code "113") (name "unconnected-(U6-A4-Pad6)") (class "Default")
      (node (ref "U6") (pin "6") (pinfunction "A4_6") (pintype "bidirectional"))
    )
    (net (code "114") (name "unconnected-(U6-A5-Pad7)") (class "Default")
      (node (ref "U6") (pin "7") (pinfunction "A5_7") (pintype "bidirectional"))
    )
    (net (code "115") (name "unconnected-(U6-A6-Pad8)") (class "Default")
      (node (ref "U6") (pin "8") (pinfunction "A6_8") (pintype "bidirectional"))
    )
    (net (code "116") (name "unconnected-(U6-A7-Pad9)") (class "Default")
      (node (ref "U6") (pin "9") (pinfunction "A7_9") (pintype "bidirectional"))
    )
    (net (code "117") (name "unconnected-(U6-B1-Pad17)") (class "Default")
      (node (ref "U6") (pin "17") (pinfunction "B1_17") (pintype "bidirectional"))
    )
    (net (code "118") (name "unconnected-(U6-B2-Pad16)") (class "Default")
      (node (ref "U6") (pin "16") (pinfunction "B2_16") (pintype "bidirectional"))
    )
    (net (code "119") (name "unconnected-(U6-B3-Pad15)") (class "Default")
      (node (ref "U6") (pin "15") (pinfunction "B3_15") (pintype "bidirectional"))
    )
    (net (code "120") (name "unconnected-(U6-B4-Pad14)") (class "Default")
      (node (ref "U6") (pin "14") (pinfunction "B4_14") (pintype "bidirectional"))
    )
    (net (code "121") (name "unconnected-(U6-B5-Pad13)") (class "Default")
      (node (ref "U6") (pin "13") (pinfunction "B5_13") (pintype "bidirectional"))
    )
    (net (code "122") (name "unconnected-(U6-B6-Pad12)") (class "Default")
      (node (ref "U6") (pin "12") (pinfunction "B6_12") (pintype "bidirectional"))
    )
    (net (code "123") (name "unconnected-(U6-B7-Pad11)") (class "Default")
      (node (ref "U6") (pin "11") (pinfunction "B7_11") (pintype "bidirectional"))
    )
  )
)
